# max_bell.net
KiCad netlist of a schematic drawn in EAGLE
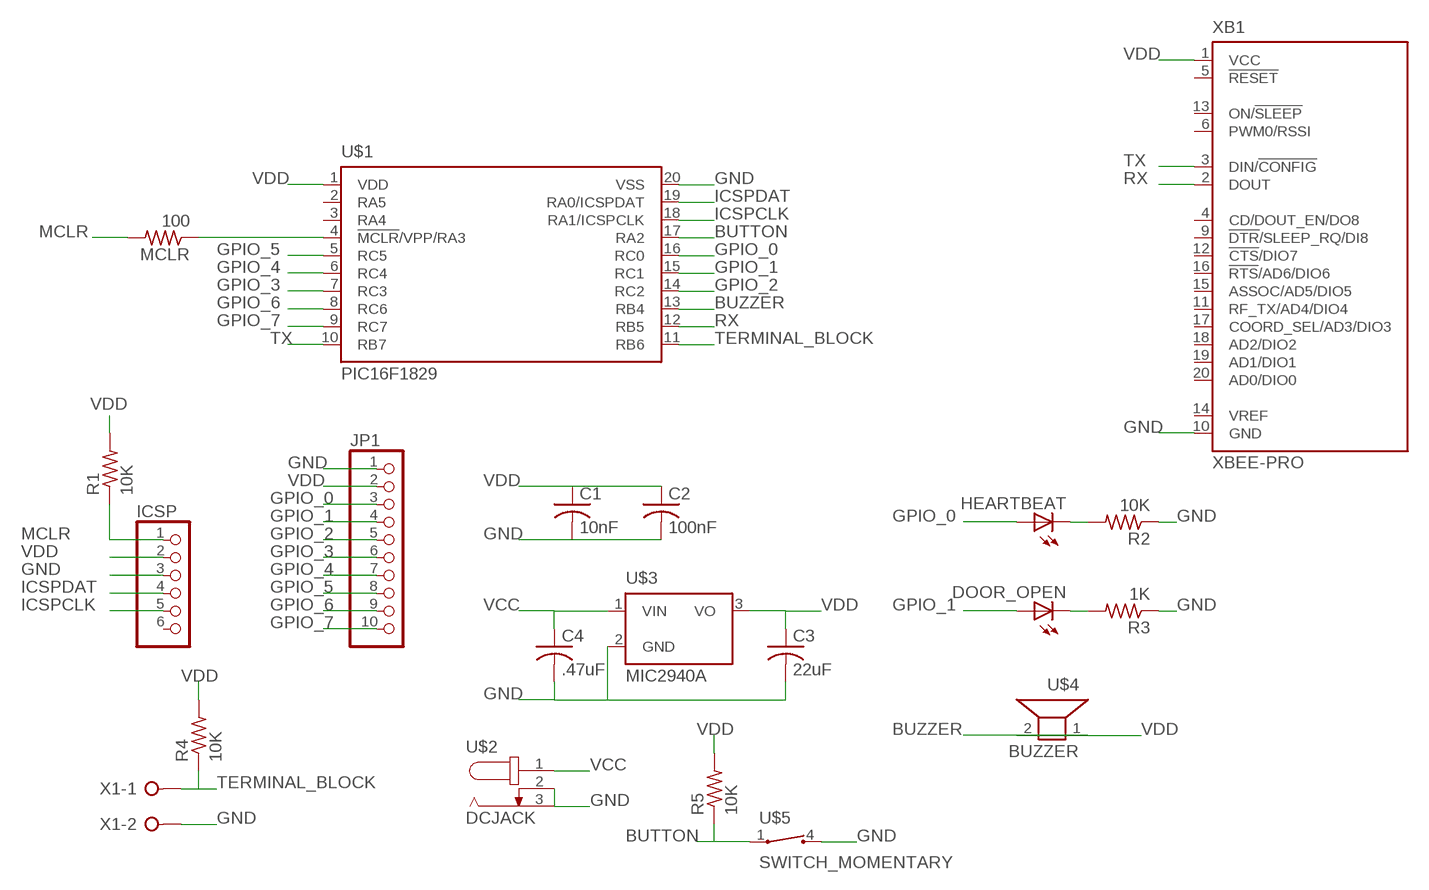
[diagram p0: schematic, sheet 1]

(export (version "E")
  (design (tool "Eeschema 10.0.6"))
  (components
    (comp (ref "C1")
      (value "10nF")
      (footprint "eagle-import:C050-035X075")
      (libsource (lib "eagle-import") (part "C-US050-035X075"))
    )
    (comp (ref "C2")
      (value "100nF")
      (footprint "eagle-import:C050-035X075")
      (libsource (lib "eagle-import") (part "C-US050-035X075"))
    )
    (comp (ref "C3")
      (value "22uF")
      (footprint "eagle-import:C050-035X075")
      (libsource (lib "eagle-import") (part "C-US050-035X075"))
    )
    (comp (ref "C4")
      (value ".47uF")
      (footprint "eagle-import:C050-035X075")
      (libsource (lib "eagle-import") (part "C-US050-035X075"))
    )
    (comp (ref "DOOR_OPEN")
      (value "LED5MM")
      (footprint "eagle-import:LED5MM")
      (libsource (lib "eagle-import") (part "LED5MM"))
    )
    (comp (ref "HEARTBEAT")
      (value "LED5MM")
      (footprint "eagle-import:LED5MM")
      (libsource (lib "eagle-import") (part "LED5MM"))
    )
    (comp (ref "ICSP")
      (value "PINHD-1X6")
      (footprint "eagle-import:1X06")
      (libsource (lib "eagle-import") (part "PINHD-1X6"))
    )
    (comp (ref "JP1")
      (value "PINHD-1X10")
      (footprint "eagle-import:1X10")
      (libsource (lib "eagle-import") (part "PINHD-1X10"))
    )
    (comp (ref "MCLR")
      (value "100")
      (footprint "eagle-import:0309_12")
      (libsource (lib "eagle-import") (part "R-US_0309/12"))
    )
    (comp (ref "R1")
      (value "10K")
      (footprint "eagle-import:0309_12")
      (libsource (lib "eagle-import") (part "R-US_0309/12"))
    )
    (comp (ref "R2")
      (value "10K")
      (footprint "eagle-import:0309_12")
      (libsource (lib "eagle-import") (part "R-US_0309/12"))
    )
    (comp (ref "R3")
      (value "1K")
      (footprint "eagle-import:0309_12")
      (libsource (lib "eagle-import") (part "R-US_0309/12"))
    )
    (comp (ref "R4")
      (value "10K")
      (footprint "eagle-import:0309_12")
      (libsource (lib "eagle-import") (part "R-US_0309/12"))
    )
    (comp (ref "R5")
      (value "10K")
      (footprint "eagle-import:0309_12")
      (libsource (lib "eagle-import") (part "R-US_0309/12"))
    )
    (comp (ref "U$1")
      (value "PIC16F1829")
      (footprint "eagle-import:DIL20")
      (libsource (lib "eagle-import") (part "PIC16F1829"))
    )
    (comp (ref "U$2")
      (value "DCJACK")
      (footprint "eagle-import:DCJACKFP")
      (libsource (lib "eagle-import") (part "DCJACK"))
    )
    (comp (ref "U$3")
      (value "MIC2940A")
      (footprint "eagle-import:TO220V")
      (libsource (lib "eagle-import") (part "MIC2940A"))
    )
    (comp (ref "U$4")
      (value "BUZZER")
      (footprint "eagle-import:BUZZER")
      (libsource (lib "eagle-import") (part "BUZZER"))
    )
    (comp (ref "U$5")
      (value "SWITCH_MOMENTARY")
      (footprint "eagle-import:MOMENTARY_SWITCH")
      (libsource (lib "eagle-import") (part "SWITCH_MOMENTARY"))
    )
    (comp (ref "X1")
      (value "W237-02P")
      (footprint "eagle-import:W237-132")
      (libsource (lib "eagle-import") (part "W237-02P"))
    )
    (comp (ref "XB1")
      (value "XBEE-PRO")
      (footprint "eagle-import:XBEE-PRO")
      (fields (field (name "MPN") "XBP24-AWI-001"))
      (libsource (lib "eagle-import") (part "XBEE-PRO"))
    )
  )
  (nets
    (net (code "1") (name "/BUTTON") (class "Default")
      (node (ref "R5") (pin "1") (pinfunction "1_1") (pintype "passive"))
      (node (ref "U$1") (pin "17") (pinfunction "RA2_17") (pintype "bidirectional"))
      (node (ref "U$5") (pin "1") (pinfunction "1_1") (pintype "passive"))
    )
    (net (code "2") (name "/BUZZER") (class "Default")
      (node (ref "U$1") (pin "13") (pinfunction "RB4_13") (pintype "bidirectional"))
      (node (ref "U$4") (pin "1") (pinfunction "1_1") (pintype "passive"))
    )
    (net (code "3") (name "/GND") (class "Default")
      (node (ref "C1") (pin "2") (pinfunction "2_2") (pintype "passive"))
      (node (ref "C2") (pin "2") (pinfunction "2_2") (pintype "passive"))
      (node (ref "C3") (pin "2") (pinfunction "2_2") (pintype "passive"))
      (node (ref "C4") (pin "2") (pinfunction "2_2") (pintype "passive"))
      (node (ref "ICSP") (pin "3") (pinfunction "3_3") (pintype "passive"))
      (node (ref "JP1") (pin "1") (pinfunction "1_1") (pintype "passive"))
      (node (ref "R2") (pin "1") (pinfunction "1_1") (pintype "passive"))
      (node (ref "R3") (pin "1") (pinfunction "1_1") (pintype "passive"))
      (node (ref "U$1") (pin "20") (pinfunction "VSS_20") (pintype "bidirectional"))
      (node (ref "U$2") (pin "2") (pinfunction "2_2") (pintype "passive"))
      (node (ref "U$2") (pin "3") (pinfunction "1_3") (pintype "passive"))
      (node (ref "U$3") (pin "2") (pinfunction "GND_2") (pintype "passive"))
      (node (ref "U$5") (pin "4") (pinfunction "2_4") (pintype "passive"))
      (node (ref "X1") (pin "2") (pinfunction "KL_2") (pintype "passive"))
      (node (ref "XB1") (pin "10") (pinfunction "GND_10") (pintype "power_in"))
    )
    (net (code "4") (name "/GPIO_0") (class "Default")
      (node (ref "HEARTBEAT") (pin "A") (pinfunction "A_A") (pintype "passive"))
      (node (ref "JP1") (pin "3") (pinfunction "3_3") (pintype "passive"))
      (node (ref "U$1") (pin "16") (pinfunction "RC0_16") (pintype "bidirectional"))
    )
    (net (code "5") (name "/GPIO_1") (class "Default")
      (node (ref "DOOR_OPEN") (pin "A") (pinfunction "A_A") (pintype "passive"))
      (node (ref "JP1") (pin "4") (pinfunction "4_4") (pintype "passive"))
      (node (ref "U$1") (pin "15") (pinfunction "RC1_15") (pintype "bidirectional"))
    )
    (net (code "6") (name "/GPIO_2") (class "Default")
      (node (ref "JP1") (pin "5") (pinfunction "5_5") (pintype "passive"))
      (node (ref "U$1") (pin "14") (pinfunction "RC2_14") (pintype "bidirectional"))
    )
    (net (code "7") (name "/GPIO_3") (class "Default")
      (node (ref "JP1") (pin "6") (pinfunction "6_6") (pintype "passive"))
      (node (ref "U$1") (pin "7") (pinfunction "RC3_7") (pintype "bidirectional"))
    )
    (net (code "8") (name "/GPIO_4") (class "Default")
      (node (ref "JP1") (pin "7") (pinfunction "7_7") (pintype "passive"))
      (node (ref "U$1") (pin "6") (pinfunction "RC4_6") (pintype "bidirectional"))
    )
    (net (code "9") (name "/GPIO_5") (class "Default")
      (node (ref "JP1") (pin "8") (pinfunction "8_8") (pintype "passive"))
      (node (ref "U$1") (pin "5") (pinfunction "RC5_5") (pintype "bidirectional"))
    )
    (net (code "10") (name "/GPIO_6") (class "Default")
      (node (ref "JP1") (pin "9") (pinfunction "9_9") (pintype "passive"))
      (node (ref "U$1") (pin "8") (pinfunction "RC6_8") (pintype "power_in"))
    )
    (net (code "11") (name "/GPIO_7") (class "Default")
      (node (ref "JP1") (pin "10") (pinfunction "10_10") (pintype "passive"))
      (node (ref "U$1") (pin "9") (pinfunction "RC7_9") (pintype "input"))
    )
    (net (code "12") (name "/ICSPCLK") (class "Default")
      (node (ref "ICSP") (pin "5") (pinfunction "5_5") (pintype "passive"))
      (node (ref "U$1") (pin "18") (pinfunction "RA1/ICSPCLK_18") (pintype "bidirectional"))
    )
    (net (code "13") (name "/ICSPDAT") (class "Default")
      (node (ref "ICSP") (pin "4") (pinfunction "4_4") (pintype "passive"))
      (node (ref "U$1") (pin "19") (pinfunction "RA0/ICSPDAT_19") (pintype "bidirectional"))
    )
    (net (code "14") (name "/MCLR") (class "Default")
      (node (ref "ICSP") (pin "1") (pinfunction "1_1") (pintype "passive"))
      (node (ref "MCLR") (pin "2") (pinfunction "2_2") (pintype "passive"))
      (node (ref "R1") (pin "1") (pinfunction "1_1") (pintype "passive"))
    )
    (net (code "15") (name "/RX") (class "Default")
      (node (ref "U$1") (pin "12") (pinfunction "RB5_12") (pintype "power_in"))
      (node (ref "XB1") (pin "2") (pinfunction "DOUT_2") (pintype "output"))
    )
    (net (code "16") (name "/TERMINAL_BLOCK") (class "Default")
      (node (ref "R4") (pin "1") (pinfunction "1_1") (pintype "passive"))
      (node (ref "U$1") (pin "11") (pinfunction "RB6_11") (pintype "power_in"))
      (node (ref "X1") (pin "1") (pinfunction "KL_1") (pintype "passive"))
    )
    (net (code "17") (name "/TX") (class "Default")
      (node (ref "U$1") (pin "10") (pinfunction "RB7_10") (pintype "output"))
      (node (ref "XB1") (pin "3") (pinfunction "DIN/~{CONFIG}_3") (pintype "input"))
    )
    (net (code "18") (name "/VCC") (class "Default")
      (node (ref "C4") (pin "1") (pinfunction "1_1") (pintype "passive"))
      (node (ref "U$2") (pin "1") (pinfunction "3_1") (pintype "passive"))
      (node (ref "U$3") (pin "1") (pinfunction "VIN_1") (pintype "input"))
    )
    (net (code "19") (name "/VDD") (class "Default")
      (node (ref "C1") (pin "1") (pinfunction "1_1") (pintype "passive"))
      (node (ref "C2") (pin "1") (pinfunction "1_1") (pintype "passive"))
      (node (ref "C3") (pin "1") (pinfunction "1_1") (pintype "passive"))
      (node (ref "ICSP") (pin "2") (pinfunction "2_2") (pintype "passive"))
      (node (ref "JP1") (pin "2") (pinfunction "2_2") (pintype "passive"))
      (node (ref "R1") (pin "2") (pinfunction "2_2") (pintype "passive"))
      (node (ref "R4") (pin "2") (pinfunction "2_2") (pintype "passive"))
      (node (ref "R5") (pin "2") (pinfunction "2_2") (pintype "passive"))
      (node (ref "U$1") (pin "1") (pinfunction "VDD_1") (pintype "input"))
      (node (ref "U$3") (pin "3") (pinfunction "VO_3") (pintype "output"))
      (node (ref "U$4") (pin "2") (pinfunction "2_2") (pintype "passive"))
      (node (ref "XB1") (pin "1") (pinfunction "VCC_1") (pintype "power_in"))
    )
    (net (code "20") (name "Net-(DOOR_OPEN-C)") (class "Default")
      (node (ref "DOOR_OPEN") (pin "K") (pinfunction "C_K") (pintype "passive"))
      (node (ref "R3") (pin "2") (pinfunction "2_2") (pintype "passive"))
    )
    (net (code "21") (name "Net-(HEARTBEAT-C)") (class "Default")
      (node (ref "HEARTBEAT") (pin "K") (pinfunction "C_K") (pintype "passive"))
      (node (ref "R2") (pin "2") (pinfunction "2_2") (pintype "passive"))
    )
    (net (code "22") (name "Net-(U$1-~{MCLR}{slash}VPP{slash}RA3)") (class "Default")
      (node (ref "MCLR") (pin "1") (pinfunction "1_1") (pintype "passive"))
      (node (ref "U$1") (pin "4") (pinfunction "~{MCLR}/VPP/RA3_4") (pintype "bidirectional"))
    )
    (net (code "23") (name "unconnected-(ICSP-Pad6)") (class "Default")
      (node (ref "ICSP") (pin "6") (pinfunction "6_6") (pintype "passive"))
    )
    (net (code "24") (name "unconnected-(U$1-RA4-Pad3)") (class "Default")
      (node (ref "U$1") (pin "3") (pinfunction "RA4_3") (pintype "bidirectional"))
    )
    (net (code "25") (name "unconnected-(U$1-RA5-Pad2)") (class "Default")
      (node (ref "U$1") (pin "2") (pinfunction "RA5_2") (pintype "bidirectional"))
    )
    (net (code "26") (name "unconnected-(XB1-AD0{slash}DIO0-Pad20)") (class "Default")
      (node (ref "XB1") (pin "20") (pinfunction "AD0/DIO0_20") (pintype "bidirectional"))
    )
    (net (code "27") (name "unconnected-(XB1-AD1{slash}DIO1-Pad19)") (class "Default")
      (node (ref "XB1") (pin "19") (pinfunction "AD1/DIO1_19") (pintype "bidirectional"))
    )
    (net (code "28") (name "unconnected-(XB1-AD2{slash}DIO2-Pad18)") (class "Default")
      (node (ref "XB1") (pin "18") (pinfunction "AD2/DIO2_18") (pintype "bidirectional"))
    )
    (net (code "29") (name "unconnected-(XB1-ASSOC{slash}AD5{slash}DIO5-Pad15)") (class "Default")
      (node (ref "XB1") (pin "15") (pinfunction "ASSOC/AD5/DIO5_15") (pintype "bidirectional"))
    )
    (net (code "30") (name "unconnected-(XB1-CD{slash}DOUT_EN{slash}DO8-Pad4)") (class "Default")
      (node (ref "XB1") (pin "4") (pinfunction "CD/DOUT_EN/DO8_4") (pintype "output"))
    )
    (net (code "31") (name "unconnected-(XB1-COORD_SEL{slash}AD3{slash}DIO3-Pad17)") (class "Default")
      (node (ref "XB1") (pin "17") (pinfunction "COORD_SEL/AD3/DIO3_17") (pintype "bidirectional"))
    )
    (net (code "32") (name "unconnected-(XB1-ON{slash}~{SLEEP}-Pad13)") (class "Default")
      (node (ref "XB1") (pin "13") (pinfunction "ON/~{SLEEP}_13") (pintype "output"))
    )
    (net (code "33") (name "unconnected-(XB1-PWM0{slash}RSSI-Pad6)") (class "Default")
      (node (ref "XB1") (pin "6") (pinfunction "PWM0/RSSI_6") (pintype "output"))
    )
    (net (code "34") (name "unconnected-(XB1-RF_TX{slash}AD4{slash}DIO4-Pad11)") (class "Default")
      (node (ref "XB1") (pin "11") (pinfunction "RF_TX/AD4/DIO4_11") (pintype "bidirectional"))
    )
    (net (code "35") (name "unconnected-(XB1-VREF-Pad14)") (class "Default")
      (node (ref "XB1") (pin "14") (pinfunction "VREF_14") (pintype "input"))
    )
    (net (code "36") (name "unconnected-(XB1-~{CTS}{slash}DIO7-Pad12)") (class "Default")
      (node (ref "XB1") (pin "12") (pinfunction "~{CTS}/DIO7_12") (pintype "bidirectional"))
    )
    (net (code "37") (name "unconnected-(XB1-~{DTR}{slash}SLEEP_RQ{slash}DI8-Pad9)") (class "Default")
      (node (ref "XB1") (pin "9") (pinfunction "~{DTR}/SLEEP_RQ/DI8_9") (pintype "bidirectional"))
    )
    (net (code "38") (name "unconnected-(XB1-~{RESET}-Pad5)") (class "Default")
      (node (ref "XB1") (pin "5") (pinfunction "~{RESET}_5") (pintype "input"))
    )
    (net (code "39") (name "unconnected-(XB1-~{RTS}{slash}AD6{slash}DIO6-Pad16)") (class "Default")
      (node (ref "XB1") (pin "16") (pinfunction "~{RTS}/AD6/DIO6_16") (pintype "bidirectional"))
    )
  )
)
